# PWM.net
KiCad netlist of a schematic drawn in Altium Designer
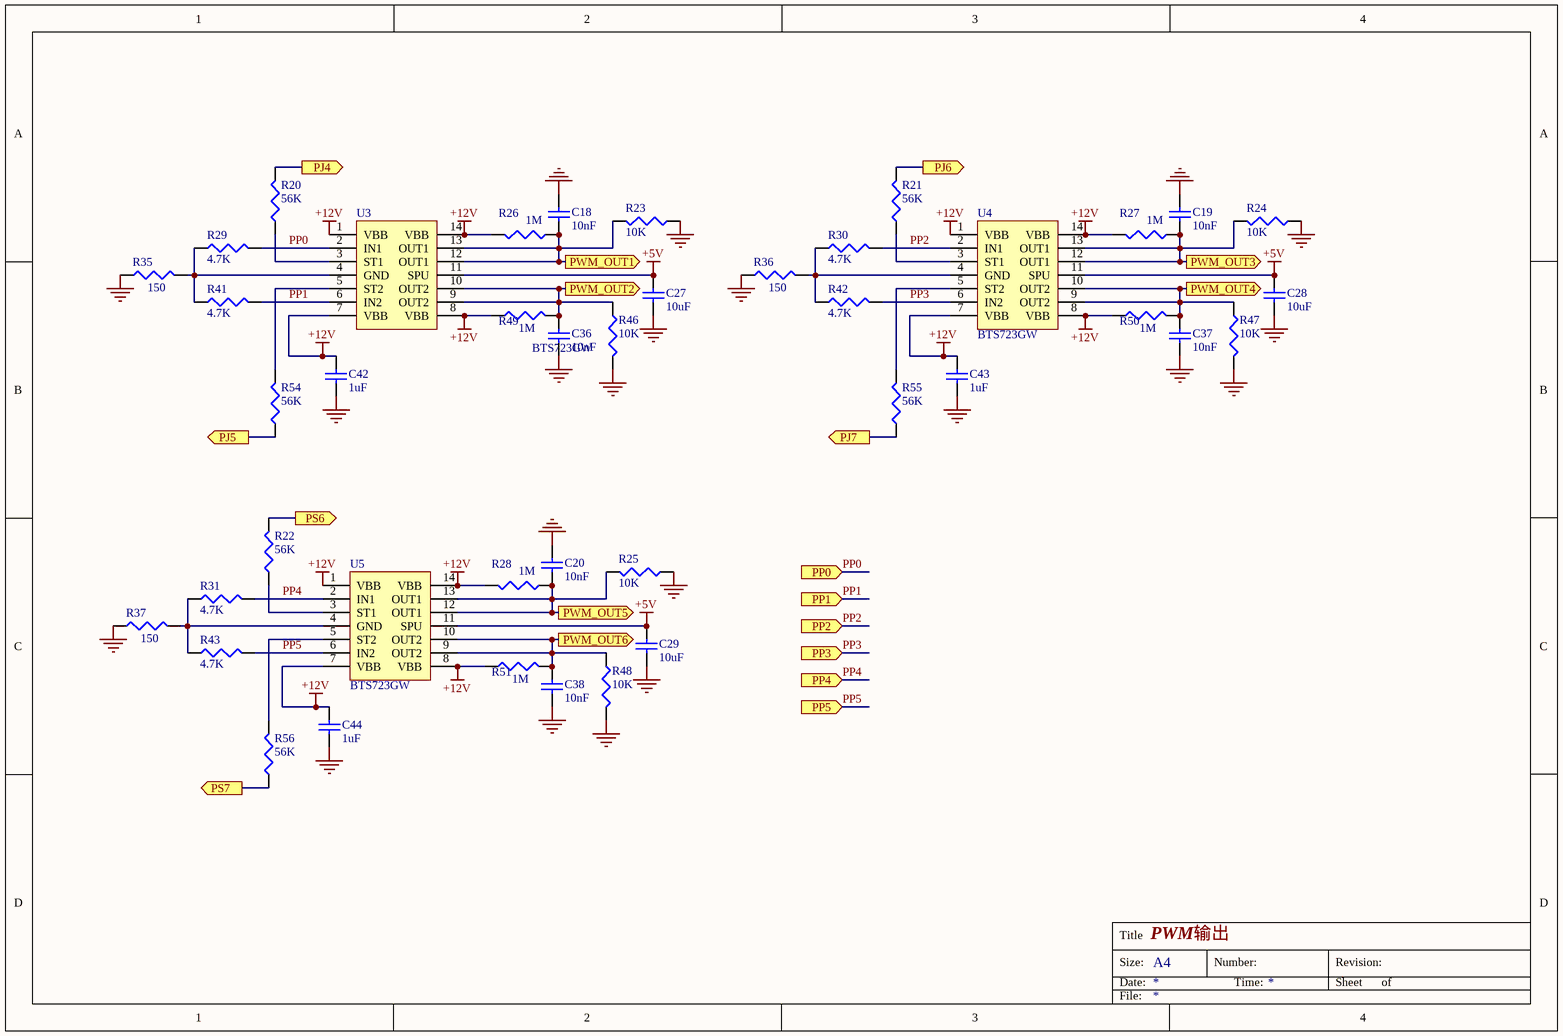
[diagram p0: PWM输出.SchDoc]

(export (version "E")
  (design (tool "Eeschema 10.0.6"))
  (components
    (comp (ref "C18")
      (value "10nF")
      (footprint "0603-L")
      (description "Capacitor")
      (fields (field (name "Comment") "Cap") (field (name "PUBLISHER") "Altium Limited"))
      (libsource (lib "Miscellaneous Devices") (part "Cap"))
    )
    (comp (ref "C19")
      (value "10nF")
      (footprint "0603-L")
      (description "Capacitor")
      (fields (field (name "Comment") "Cap") (field (name "PUBLISHER") "Altium Limited"))
      (libsource (lib "Miscellaneous Devices") (part "Cap"))
    )
    (comp (ref "C20")
      (value "10nF")
      (footprint "0603-L")
      (description "Capacitor")
      (fields (field (name "Comment") "Cap") (field (name "PUBLISHER") "Altium Limited"))
      (libsource (lib "Miscellaneous Devices") (part "Cap"))
    )
    (comp (ref "C27")
      (value "10uF")
      (footprint "0603-L")
      (description "Capacitor")
      (fields (field (name "Comment") "Cap") (field (name "PUBLISHER") "Altium Limited"))
      (libsource (lib "Miscellaneous Devices") (part "Cap"))
    )
    (comp (ref "C28")
      (value "10uF")
      (footprint "0603-L")
      (description "Capacitor")
      (fields (field (name "Comment") "Cap") (field (name "PUBLISHER") "Altium Limited"))
      (libsource (lib "Miscellaneous Devices") (part "Cap"))
    )
    (comp (ref "C29")
      (value "10uF")
      (footprint "0603-L")
      (description "Capacitor")
      (fields (field (name "Comment") "Cap") (field (name "PUBLISHER") "Altium Limited"))
      (libsource (lib "Miscellaneous Devices") (part "Cap"))
    )
    (comp (ref "C36")
      (value "10nF")
      (footprint "0603-L")
      (description "Capacitor")
      (fields (field (name "Comment") "Cap") (field (name "PUBLISHER") "Altium Limited"))
      (libsource (lib "Miscellaneous Devices") (part "Cap"))
    )
    (comp (ref "C37")
      (value "10nF")
      (footprint "0603-L")
      (description "Capacitor")
      (fields (field (name "Comment") "Cap") (field (name "PUBLISHER") "Altium Limited"))
      (libsource (lib "Miscellaneous Devices") (part "Cap"))
    )
    (comp (ref "C38")
      (value "10nF")
      (footprint "0603-L")
      (description "Capacitor")
      (fields (field (name "Comment") "Cap") (field (name "PUBLISHER") "Altium Limited"))
      (libsource (lib "Miscellaneous Devices") (part "Cap"))
    )
    (comp (ref "C42")
      (value "1uF")
      (footprint "0603-L")
      (description "Capacitor")
      (fields (field (name "Comment") "Cap") (field (name "PUBLISHER") "Altium Limited"))
      (libsource (lib "Miscellaneous Devices") (part "Cap"))
    )
    (comp (ref "C43")
      (value "1uF")
      (footprint "0603-L")
      (description "Capacitor")
      (fields (field (name "Comment") "Cap") (field (name "PUBLISHER") "Altium Limited"))
      (libsource (lib "Miscellaneous Devices") (part "Cap"))
    )
    (comp (ref "C44")
      (value "1uF")
      (footprint "0603-L")
      (description "Capacitor")
      (fields (field (name "Comment") "Cap") (field (name "PUBLISHER") "Altium Limited"))
      (libsource (lib "Miscellaneous Devices") (part "Cap"))
    )
    (comp (ref "R20")
      (value "56K")
      (footprint "0603-L")
      (description "Resistor")
      (fields (field (name "Comment") "Res3") (field (name "PUBLISHER") "Altium Limited"))
      (libsource (lib "Miscellaneous Devices") (part "Res3"))
    )
    (comp (ref "R21")
      (value "56K")
      (footprint "0603-L")
      (description "Resistor")
      (fields (field (name "Comment") "Res3") (field (name "PUBLISHER") "Altium Limited"))
      (libsource (lib "Miscellaneous Devices") (part "Res3"))
    )
    (comp (ref "R22")
      (value "56K")
      (footprint "0603-L")
      (description "Resistor")
      (fields (field (name "Comment") "Res3") (field (name "PUBLISHER") "Altium Limited"))
      (libsource (lib "Miscellaneous Devices") (part "Res3"))
    )
    (comp (ref "R23")
      (value "10K")
      (footprint "0603-L")
      (description "Resistor")
      (fields (field (name "Comment") "Res3") (field (name "PUBLISHER") "Altium Limited"))
      (libsource (lib "Miscellaneous Devices") (part "Res3"))
    )
    (comp (ref "R24")
      (value "10K")
      (footprint "0603-L")
      (description "Resistor")
      (fields (field (name "Comment") "Res3") (field (name "PUBLISHER") "Altium Limited"))
      (libsource (lib "Miscellaneous Devices") (part "Res3"))
    )
    (comp (ref "R25")
      (value "10K")
      (footprint "0603-L")
      (description "Resistor")
      (fields (field (name "Comment") "Res3") (field (name "PUBLISHER") "Altium Limited"))
      (libsource (lib "Miscellaneous Devices") (part "Res3"))
    )
    (comp (ref "R26")
      (value "1M")
      (footprint "0603-L")
      (description "Resistor")
      (fields (field (name "Comment") "Res3") (field (name "PUBLISHER") "Altium Limited"))
      (libsource (lib "Miscellaneous Devices") (part "Res3"))
    )
    (comp (ref "R27")
      (value "1M")
      (footprint "0603-L")
      (description "Resistor")
      (fields (field (name "Comment") "Res3") (field (name "PUBLISHER") "Altium Limited"))
      (libsource (lib "Miscellaneous Devices") (part "Res3"))
    )
    (comp (ref "R28")
      (value "1M")
      (footprint "0603-L")
      (description "Resistor")
      (fields (field (name "Comment") "Res3") (field (name "PUBLISHER") "Altium Limited"))
      (libsource (lib "Miscellaneous Devices") (part "Res3"))
    )
    (comp (ref "R29")
      (value "4.7K")
      (footprint "0603-L")
      (description "Resistor")
      (fields (field (name "Comment") "Res3") (field (name "PUBLISHER") "Altium Limited"))
      (libsource (lib "Miscellaneous Devices") (part "Res3"))
    )
    (comp (ref "R30")
      (value "4.7K")
      (footprint "0603-L")
      (description "Resistor")
      (fields (field (name "Comment") "Res3") (field (name "PUBLISHER") "Altium Limited"))
      (libsource (lib "Miscellaneous Devices") (part "Res3"))
    )
    (comp (ref "R31")
      (value "4.7K")
      (footprint "0603-L")
      (description "Resistor")
      (fields (field (name "Comment") "Res3") (field (name "PUBLISHER") "Altium Limited"))
      (libsource (lib "Miscellaneous Devices") (part "Res3"))
    )
    (comp (ref "R35")
      (value "150")
      (footprint "RES1206")
      (description "Resistor")
      (fields (field (name "Comment") "Res3") (field (name "PUBLISHER") "Altium Limited"))
      (libsource (lib "Miscellaneous Devices") (part "Res3"))
    )
    (comp (ref "R36")
      (value "150")
      (footprint "RES1206")
      (description "Resistor")
      (fields (field (name "Comment") "Res3") (field (name "PUBLISHER") "Altium Limited"))
      (libsource (lib "Miscellaneous Devices") (part "Res3"))
    )
    (comp (ref "R37")
      (value "150")
      (footprint "RES1206")
      (description "Resistor")
      (fields (field (name "Comment") "Res3") (field (name "PUBLISHER") "Altium Limited"))
      (libsource (lib "Miscellaneous Devices") (part "Res3"))
    )
    (comp (ref "R41")
      (value "4.7K")
      (footprint "0603-L")
      (description "Resistor")
      (fields (field (name "Comment") "Res3") (field (name "PUBLISHER") "Altium Limited"))
      (libsource (lib "Miscellaneous Devices") (part "Res3"))
    )
    (comp (ref "R42")
      (value "4.7K")
      (footprint "0603-L")
      (description "Resistor")
      (fields (field (name "Comment") "Res3") (field (name "PUBLISHER") "Altium Limited"))
      (libsource (lib "Miscellaneous Devices") (part "Res3"))
    )
    (comp (ref "R43")
      (value "4.7K")
      (footprint "0603-L")
      (description "Resistor")
      (fields (field (name "Comment") "Res3") (field (name "PUBLISHER") "Altium Limited"))
      (libsource (lib "Miscellaneous Devices") (part "Res3"))
    )
    (comp (ref "R46")
      (value "10K")
      (footprint "0603-L")
      (description "Resistor")
      (fields (field (name "Comment") "Res3") (field (name "PUBLISHER") "Altium Limited"))
      (libsource (lib "Miscellaneous Devices") (part "Res3"))
    )
    (comp (ref "R47")
      (value "10K")
      (footprint "0603-L")
      (description "Resistor")
      (fields (field (name "Comment") "Res3") (field (name "PUBLISHER") "Altium Limited"))
      (libsource (lib "Miscellaneous Devices") (part "Res3"))
    )
    (comp (ref "R48")
      (value "10K")
      (footprint "0603-L")
      (description "Resistor")
      (fields (field (name "Comment") "Res3") (field (name "PUBLISHER") "Altium Limited"))
      (libsource (lib "Miscellaneous Devices") (part "Res3"))
    )
    (comp (ref "R49")
      (value "1M")
      (footprint "0603-L")
      (description "Resistor")
      (fields (field (name "Comment") "Res3") (field (name "PUBLISHER") "Altium Limited"))
      (libsource (lib "Miscellaneous Devices") (part "Res3"))
    )
    (comp (ref "R50")
      (value "1M")
      (footprint "0603-L")
      (description "Resistor")
      (fields (field (name "Comment") "Res3") (field (name "PUBLISHER") "Altium Limited"))
      (libsource (lib "Miscellaneous Devices") (part "Res3"))
    )
    (comp (ref "R51")
      (value "1M")
      (footprint "0603-L")
      (description "Resistor")
      (fields (field (name "Comment") "Res3") (field (name "PUBLISHER") "Altium Limited"))
      (libsource (lib "Miscellaneous Devices") (part "Res3"))
    )
    (comp (ref "R54")
      (value "56K")
      (footprint "0603-L")
      (description "Resistor")
      (fields (field (name "Comment") "Res3") (field (name "PUBLISHER") "Altium Limited"))
      (libsource (lib "Miscellaneous Devices") (part "Res3"))
    )
    (comp (ref "R55")
      (value "56K")
      (footprint "0603-L")
      (description "Resistor")
      (fields (field (name "Comment") "Res3") (field (name "PUBLISHER") "Altium Limited"))
      (libsource (lib "Miscellaneous Devices") (part "Res3"))
    )
    (comp (ref "R56")
      (value "56K")
      (footprint "0603-L")
      (description "Resistor")
      (fields (field (name "Comment") "Res3") (field (name "PUBLISHER") "Altium Limited"))
      (libsource (lib "Miscellaneous Devices") (part "Res3"))
    )
    (comp (ref "U3") (value "BTS723GW") (footprint "BTS723GW") (libsource (lib "整车控制器") (part "BTS723GW")))
    (comp (ref "U4") (value "BTS723GW") (footprint "BTS723GW") (libsource (lib "整车控制器") (part "BTS723GW")))
    (comp (ref "U5") (value "BTS723GW") (footprint "BTS723GW") (libsource (lib "整车控制器") (part "BTS723GW")))
  )
  (nets
    (net (code "1") (name "+5V") (class "Default")
      (node (ref "C27") (pin "1") (pinfunction "1_1") (pintype "passive"))
      (node (ref "C28") (pin "1") (pinfunction "1_1") (pintype "passive"))
      (node (ref "C29") (pin "1") (pinfunction "1_1") (pintype "passive"))
      (node (ref "U3") (pin "11") (pinfunction "SPU_11") (pintype "passive"))
      (node (ref "U4") (pin "11") (pinfunction "SPU_11") (pintype "passive"))
      (node (ref "U5") (pin "11") (pinfunction "SPU_11") (pintype "passive"))
    )
    (net (code "2") (name "+12V") (class "Default")
      (node (ref "C42") (pin "1") (pinfunction "1_1") (pintype "passive"))
      (node (ref "C43") (pin "1") (pinfunction "1_1") (pintype "passive"))
      (node (ref "C44") (pin "1") (pinfunction "1_1") (pintype "passive"))
      (node (ref "R26") (pin "1") (pinfunction "1_1") (pintype "passive"))
      (node (ref "R27") (pin "1") (pinfunction "1_1") (pintype "passive"))
      (node (ref "R28") (pin "1") (pinfunction "1_1") (pintype "passive"))
      (node (ref "R49") (pin "1") (pinfunction "1_1") (pintype "passive"))
      (node (ref "R50") (pin "1") (pinfunction "1_1") (pintype "passive"))
      (node (ref "R51") (pin "1") (pinfunction "1_1") (pintype "passive"))
      (node (ref "U3") (pin "1") (pinfunction "VBB_1") (pintype "passive"))
      (node (ref "U3") (pin "14") (pinfunction "VBB_14") (pintype "passive"))
      (node (ref "U3") (pin "7") (pinfunction "VBB_7") (pintype "passive"))
      (node (ref "U3") (pin "8") (pinfunction "VBB_8") (pintype "passive"))
      (node (ref "U4") (pin "1") (pinfunction "VBB_1") (pintype "passive"))
      (node (ref "U4") (pin "14") (pinfunction "VBB_14") (pintype "passive"))
      (node (ref "U4") (pin "7") (pinfunction "VBB_7") (pintype "passive"))
      (node (ref "U4") (pin "8") (pinfunction "VBB_8") (pintype "passive"))
      (node (ref "U5") (pin "1") (pinfunction "VBB_1") (pintype "passive"))
      (node (ref "U5") (pin "14") (pinfunction "VBB_14") (pintype "passive"))
      (node (ref "U5") (pin "7") (pinfunction "VBB_7") (pintype "passive"))
      (node (ref "U5") (pin "8") (pinfunction "VBB_8") (pintype "passive"))
    )
    (net (code "3") (name "/PJ4") (class "Default")
      (node (ref "R20") (pin "2") (pinfunction "2_2") (pintype "passive"))
    )
    (net (code "4") (name "/PJ5") (class "Default")
      (node (ref "R54") (pin "1") (pinfunction "1_1") (pintype "passive"))
    )
    (net (code "5") (name "/PJ6") (class "Default")
      (node (ref "R21") (pin "2") (pinfunction "2_2") (pintype "passive"))
    )
    (net (code "6") (name "/PJ7") (class "Default")
      (node (ref "R55") (pin "1") (pinfunction "1_1") (pintype "passive"))
    )
    (net (code "7") (name "/PP0") (class "Default")
      (node (ref "R29") (pin "2") (pinfunction "2_2") (pintype "passive"))
      (node (ref "U3") (pin "2") (pinfunction "IN1_2") (pintype "passive"))
    )
    (net (code "8") (name "/PP1") (class "Default")
      (node (ref "R41") (pin "2") (pinfunction "2_2") (pintype "passive"))
      (node (ref "U3") (pin "6") (pinfunction "IN2_6") (pintype "passive"))
    )
    (net (code "9") (name "/PP2") (class "Default")
      (node (ref "R30") (pin "2") (pinfunction "2_2") (pintype "passive"))
      (node (ref "U4") (pin "2") (pinfunction "IN1_2") (pintype "passive"))
    )
    (net (code "10") (name "/PP3") (class "Default")
      (node (ref "R42") (pin "2") (pinfunction "2_2") (pintype "passive"))
      (node (ref "U4") (pin "6") (pinfunction "IN2_6") (pintype "passive"))
    )
    (net (code "11") (name "/PP4") (class "Default")
      (node (ref "R31") (pin "2") (pinfunction "2_2") (pintype "passive"))
      (node (ref "U5") (pin "2") (pinfunction "IN1_2") (pintype "passive"))
    )
    (net (code "12") (name "/PP5") (class "Default")
      (node (ref "R43") (pin "2") (pinfunction "2_2") (pintype "passive"))
      (node (ref "U5") (pin "6") (pinfunction "IN2_6") (pintype "passive"))
    )
    (net (code "13") (name "/PS6") (class "Default")
      (node (ref "R22") (pin "2") (pinfunction "2_2") (pintype "passive"))
    )
    (net (code "14") (name "/PS7") (class "Default")
      (node (ref "R56") (pin "1") (pinfunction "1_1") (pintype "passive"))
    )
    (net (code "15") (name "/PWM_OUT1") (class "Default")
      (node (ref "C18") (pin "1") (pinfunction "1_1") (pintype "passive"))
      (node (ref "R23") (pin "1") (pinfunction "1_1") (pintype "passive"))
      (node (ref "R26") (pin "2") (pinfunction "2_2") (pintype "passive"))
      (node (ref "U3") (pin "12") (pinfunction "OUT1_12") (pintype "passive"))
      (node (ref "U3") (pin "13") (pinfunction "OUT1_13") (pintype "passive"))
    )
    (net (code "16") (name "/PWM_OUT2") (class "Default")
      (node (ref "C36") (pin "1") (pinfunction "1_1") (pintype "passive"))
      (node (ref "R46") (pin "2") (pinfunction "2_2") (pintype "passive"))
      (node (ref "R49") (pin "2") (pinfunction "2_2") (pintype "passive"))
      (node (ref "U3") (pin "10") (pinfunction "OUT2_10") (pintype "passive"))
      (node (ref "U3") (pin "9") (pinfunction "OUT2_9") (pintype "passive"))
    )
    (net (code "17") (name "/PWM_OUT3") (class "Default")
      (node (ref "C19") (pin "1") (pinfunction "1_1") (pintype "passive"))
      (node (ref "R24") (pin "1") (pinfunction "1_1") (pintype "passive"))
      (node (ref "R27") (pin "2") (pinfunction "2_2") (pintype "passive"))
      (node (ref "U4") (pin "12") (pinfunction "OUT1_12") (pintype "passive"))
      (node (ref "U4") (pin "13") (pinfunction "OUT1_13") (pintype "passive"))
    )
    (net (code "18") (name "/PWM_OUT4") (class "Default")
      (node (ref "C37") (pin "1") (pinfunction "1_1") (pintype "passive"))
      (node (ref "R47") (pin "2") (pinfunction "2_2") (pintype "passive"))
      (node (ref "R50") (pin "2") (pinfunction "2_2") (pintype "passive"))
      (node (ref "U4") (pin "10") (pinfunction "OUT2_10") (pintype "passive"))
      (node (ref "U4") (pin "9") (pinfunction "OUT2_9") (pintype "passive"))
    )
    (net (code "19") (name "/PWM_OUT5") (class "Default")
      (node (ref "C20") (pin "1") (pinfunction "1_1") (pintype "passive"))
      (node (ref "R25") (pin "1") (pinfunction "1_1") (pintype "passive"))
      (node (ref "R28") (pin "2") (pinfunction "2_2") (pintype "passive"))
      (node (ref "U5") (pin "12") (pinfunction "OUT1_12") (pintype "passive"))
      (node (ref "U5") (pin "13") (pinfunction "OUT1_13") (pintype "passive"))
    )
    (net (code "20") (name "/PWM_OUT6") (class "Default")
      (node (ref "C38") (pin "1") (pinfunction "1_1") (pintype "passive"))
      (node (ref "R48") (pin "2") (pinfunction "2_2") (pintype "passive"))
      (node (ref "R51") (pin "2") (pinfunction "2_2") (pintype "passive"))
      (node (ref "U5") (pin "10") (pinfunction "OUT2_10") (pintype "passive"))
      (node (ref "U5") (pin "9") (pinfunction "OUT2_9") (pintype "passive"))
    )
    (net (code "21") (name "GND") (class "Default")
      (node (ref "C18") (pin "2") (pinfunction "2_2") (pintype "passive"))
      (node (ref "C19") (pin "2") (pinfunction "2_2") (pintype "passive"))
      (node (ref "C20") (pin "2") (pinfunction "2_2") (pintype "passive"))
      (node (ref "C27") (pin "2") (pinfunction "2_2") (pintype "passive"))
      (node (ref "C28") (pin "2") (pinfunction "2_2") (pintype "passive"))
      (node (ref "C29") (pin "2") (pinfunction "2_2") (pintype "passive"))
      (node (ref "C36") (pin "2") (pinfunction "2_2") (pintype "passive"))
      (node (ref "C37") (pin "2") (pinfunction "2_2") (pintype "passive"))
      (node (ref "C38") (pin "2") (pinfunction "2_2") (pintype "passive"))
      (node (ref "C42") (pin "2") (pinfunction "2_2") (pintype "passive"))
      (node (ref "C43") (pin "2") (pinfunction "2_2") (pintype "passive"))
      (node (ref "C44") (pin "2") (pinfunction "2_2") (pintype "passive"))
      (node (ref "R23") (pin "2") (pinfunction "2_2") (pintype "passive"))
      (node (ref "R24") (pin "2") (pinfunction "2_2") (pintype "passive"))
      (node (ref "R25") (pin "2") (pinfunction "2_2") (pintype "passive"))
      (node (ref "R35") (pin "1") (pinfunction "1_1") (pintype "passive"))
      (node (ref "R36") (pin "1") (pinfunction "1_1") (pintype "passive"))
      (node (ref "R37") (pin "1") (pinfunction "1_1") (pintype "passive"))
      (node (ref "R46") (pin "1") (pinfunction "1_1") (pintype "passive"))
      (node (ref "R47") (pin "1") (pinfunction "1_1") (pintype "passive"))
      (node (ref "R48") (pin "1") (pinfunction "1_1") (pintype "passive"))
    )
    (net (code "22") (name "Net-(U3-GND)") (class "Default")
      (node (ref "R29") (pin "1") (pinfunction "1_1") (pintype "passive"))
      (node (ref "R35") (pin "2") (pinfunction "2_2") (pintype "passive"))
      (node (ref "R41") (pin "1") (pinfunction "1_1") (pintype "passive"))
      (node (ref "U3") (pin "4") (pinfunction "GND_4") (pintype "passive"))
    )
    (net (code "23") (name "Net-(U3-ST1)") (class "Default")
      (node (ref "R20") (pin "1") (pinfunction "1_1") (pintype "passive"))
      (node (ref "U3") (pin "3") (pinfunction "ST1_3") (pintype "passive"))
    )
    (net (code "24") (name "Net-(U3-ST2)") (class "Default")
      (node (ref "R54") (pin "2") (pinfunction "2_2") (pintype "passive"))
      (node (ref "U3") (pin "5") (pinfunction "ST2_5") (pintype "passive"))
    )
    (net (code "25") (name "Net-(U4-GND)") (class "Default")
      (node (ref "R30") (pin "1") (pinfunction "1_1") (pintype "passive"))
      (node (ref "R36") (pin "2") (pinfunction "2_2") (pintype "passive"))
      (node (ref "R42") (pin "1") (pinfunction "1_1") (pintype "passive"))
      (node (ref "U4") (pin "4") (pinfunction "GND_4") (pintype "passive"))
    )
    (net (code "26") (name "Net-(U4-ST1)") (class "Default")
      (node (ref "R21") (pin "1") (pinfunction "1_1") (pintype "passive"))
      (node (ref "U4") (pin "3") (pinfunction "ST1_3") (pintype "passive"))
    )
    (net (code "27") (name "Net-(U4-ST2)") (class "Default")
      (node (ref "R55") (pin "2") (pinfunction "2_2") (pintype "passive"))
      (node (ref "U4") (pin "5") (pinfunction "ST2_5") (pintype "passive"))
    )
    (net (code "28") (name "Net-(U5-GND)") (class "Default")
      (node (ref "R31") (pin "1") (pinfunction "1_1") (pintype "passive"))
      (node (ref "R37") (pin "2") (pinfunction "2_2") (pintype "passive"))
      (node (ref "R43") (pin "1") (pinfunction "1_1") (pintype "passive"))
      (node (ref "U5") (pin "4") (pinfunction "GND_4") (pintype "passive"))
    )
    (net (code "29") (name "Net-(U5-ST1)") (class "Default")
      (node (ref "R22") (pin "1") (pinfunction "1_1") (pintype "passive"))
      (node (ref "U5") (pin "3") (pinfunction "ST1_3") (pintype "passive"))
    )
    (net (code "30") (name "Net-(U5-ST2)") (class "Default")
      (node (ref "R56") (pin "2") (pinfunction "2_2") (pintype "passive"))
      (node (ref "U5") (pin "5") (pinfunction "ST2_5") (pintype "passive"))
    )
  )
)
